# Board.net
KiCad netlist of a schematic drawn in EAGLE
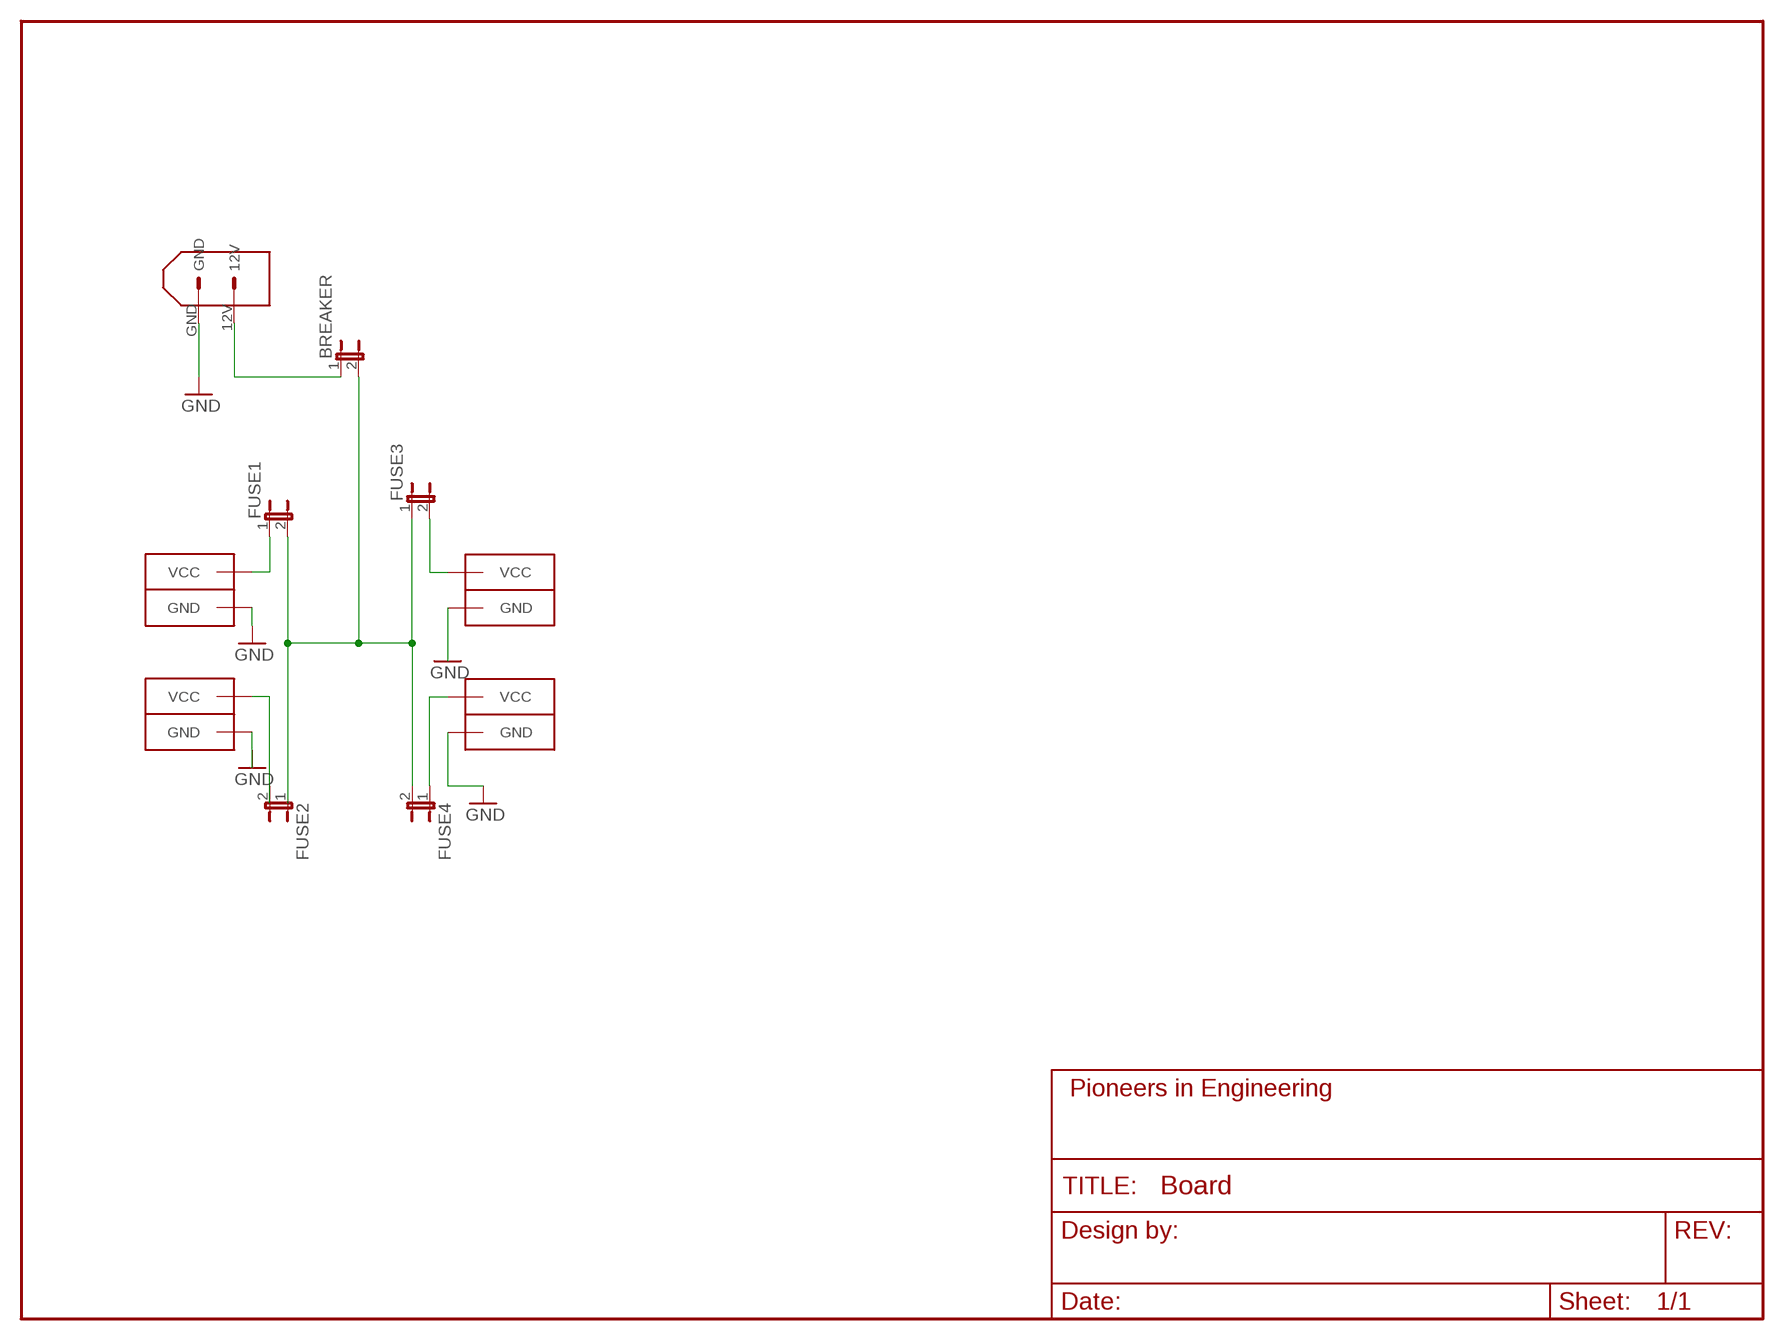
[diagram p0: schematic, sheet 1]

(export (version "E")
  (design (tool "Eeschema 10.0.6"))
  (components
    (comp (ref "BREAKER")
      (value "JP1E")
      (footprint "eagle-import:JP1")
      (libsource (lib "eagle-import") (part "JP1E"))
    )
    (comp (ref "CONN1")
      (value "ANDERSONHORIZONTAL")
      (footprint "eagle-import:ANDERSON_HORIZONTAL")
      (libsource (lib "eagle-import") (part "ANDERSONHORIZONTAL"))
    )
    (comp (ref "CONN2")
      (value "ANDERSONHORIZONTAL")
      (footprint "eagle-import:ANDERSON_HORIZONTAL")
      (libsource (lib "eagle-import") (part "ANDERSONHORIZONTAL"))
    )
    (comp (ref "CONN4")
      (value "ANDERSONHORIZONTAL")
      (footprint "eagle-import:ANDERSON_HORIZONTAL")
      (libsource (lib "eagle-import") (part "ANDERSONHORIZONTAL"))
    )
    (comp (ref "CONN5")
      (value "ANDERSONHORIZONTAL")
      (footprint "eagle-import:ANDERSON_HORIZONTAL")
      (libsource (lib "eagle-import") (part "ANDERSONHORIZONTAL"))
    )
    (comp (ref "FUSE1")
      (value "JP1E")
      (footprint "eagle-import:JP1")
      (libsource (lib "eagle-import") (part "JP1E"))
    )
    (comp (ref "FUSE2")
      (value "JP1E")
      (footprint "eagle-import:JP1")
      (libsource (lib "eagle-import") (part "JP1E"))
    )
    (comp (ref "FUSE3")
      (value "JP1E")
      (footprint "eagle-import:JP1")
      (libsource (lib "eagle-import") (part "JP1E"))
    )
    (comp (ref "FUSE4")
      (value "JP1E")
      (footprint "eagle-import:JP1")
      (libsource (lib "eagle-import") (part "JP1E"))
    )
    (comp (ref "U$1")
      (value "XT60CONNECTOR")
      (footprint "eagle-import:XT60CONNECTOR")
      (fields (field (name "PARTNUMBER") "PRT-10474 "))
      (libsource (lib "eagle-import") (part "XT60CONNECTOR"))
    )
  )
  (nets
    (net (code "1") (name "/12V") (class "Default")
      (node (ref "BREAKER") (pin "1") (pinfunction "1_1") (pintype "passive"))
      (node (ref "BREAKER") (pin "2") (pinfunction "2_2") (pintype "passive"))
      (node (ref "FUSE1") (pin "2") (pinfunction "2_2") (pintype "passive"))
      (node (ref "FUSE3") (pin "1") (pinfunction "1_1") (pintype "passive"))
      (node (ref "FUSE4") (pin "2") (pinfunction "2_2") (pintype "passive"))
      (node (ref "U$1") (pin "12V") (pinfunction "12V_12V") (pintype "bidirectional"))
    )
    (net (code "2") (name "GND") (class "Default")
      (node (ref "CONN2") (pin "PIN1") (pinfunction "GND_PIN1") (pintype "bidirectional"))
      (node (ref "CONN2") (pin "PIN1-LEAD") (pinfunction "GND_PIN1-LEAD") (pintype "bidirectional"))
      (node (ref "CONN5") (pin "PIN1") (pinfunction "GND_PIN1") (pintype "bidirectional"))
      (node (ref "CONN5") (pin "PIN1-LEAD") (pinfunction "GND_PIN1-LEAD") (pintype "bidirectional"))
      (node (ref "U$1") (pin "GND") (pinfunction "GND_GND") (pintype "bidirectional"))
    )
    (net (code "3") (name "Net-(CONN1-GND-PadPIN1)") (class "Default")
      (node (ref "CONN1") (pin "PIN1") (pinfunction "GND_PIN1") (pintype "bidirectional"))
      (node (ref "CONN1") (pin "PIN1-LEAD") (pinfunction "GND_PIN1-LEAD") (pintype "bidirectional"))
    )
    (net (code "4") (name "Net-(CONN1-VCC-PadPIN2)") (class "Default")
      (node (ref "CONN1") (pin "PIN2") (pinfunction "VCC_PIN2") (pintype "bidirectional"))
      (node (ref "CONN1") (pin "PIN2-LEAD") (pinfunction "VCC_PIN2-LEAD") (pintype "bidirectional"))
    )
    (net (code "5") (name "Net-(CONN2-VCC-PadPIN2)") (class "Default")
      (node (ref "CONN2") (pin "PIN2") (pinfunction "VCC_PIN2") (pintype "bidirectional"))
      (node (ref "CONN2") (pin "PIN2-LEAD") (pinfunction "VCC_PIN2-LEAD") (pintype "bidirectional"))
      (node (ref "FUSE1") (pin "1") (pinfunction "1_1") (pintype "passive"))
    )
    (net (code "6") (name "Net-(CONN4-GND-PadPIN1)") (class "Default")
      (node (ref "CONN4") (pin "PIN1") (pinfunction "GND_PIN1") (pintype "bidirectional"))
      (node (ref "CONN4") (pin "PIN1-LEAD") (pinfunction "GND_PIN1-LEAD") (pintype "bidirectional"))
    )
    (net (code "7") (name "Net-(CONN4-VCC-PadPIN2)") (class "Default")
      (node (ref "CONN4") (pin "PIN2") (pinfunction "VCC_PIN2") (pintype "bidirectional"))
      (node (ref "CONN4") (pin "PIN2-LEAD") (pinfunction "VCC_PIN2-LEAD") (pintype "bidirectional"))
      (node (ref "FUSE3") (pin "2") (pinfunction "2_2") (pintype "passive"))
    )
    (net (code "8") (name "Net-(CONN5-VCC-PadPIN2)") (class "Default")
      (node (ref "CONN5") (pin "PIN2") (pinfunction "VCC_PIN2") (pintype "bidirectional"))
      (node (ref "CONN5") (pin "PIN2-LEAD") (pinfunction "VCC_PIN2-LEAD") (pintype "bidirectional"))
      (node (ref "FUSE4") (pin "1") (pinfunction "1_1") (pintype "passive"))
    )
    (net (code "9") (name "unconnected-(FUSE2-Pad1)") (class "Default")
      (node (ref "FUSE2") (pin "1") (pinfunction "1_1") (pintype "passive"))
    )
    (net (code "10") (name "unconnected-(FUSE2-Pad2)") (class "Default")
      (node (ref "FUSE2") (pin "2") (pinfunction "2_2") (pintype "passive"))
    )
  )
)
